# XMOS_TSBOARD_Clock.net
KiCad netlist of a schematic drawn in Altium Designer
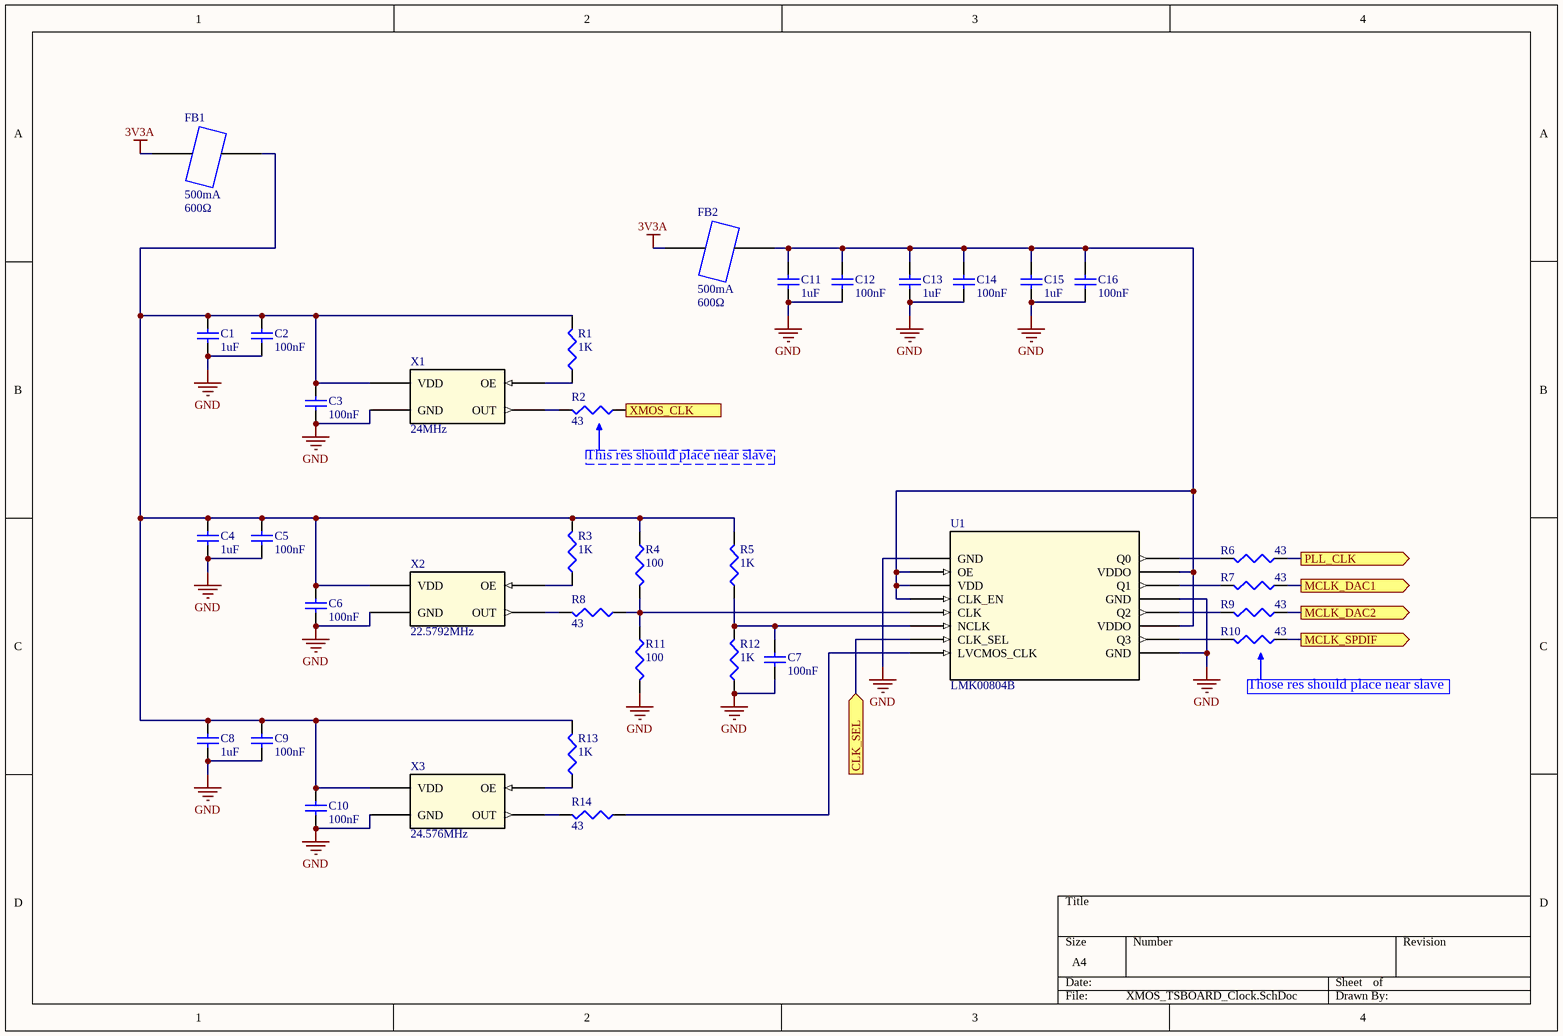
[diagram p0: XMOS_TSBOARD_Clock.SchDoc]

(export (version "E")
  (design (tool "Eeschema 10.0.6"))
  (components
    (comp (ref "C1")
      (value "1uF")
      (footprint "1608[0603]")
      (description "Capacitor (Semiconductor SIM Model)")
      (fields (field (name "Comment") "Cap Semi") (field (name "PUBLISHER") "Altium Limited"))
      (libsource (lib "Miscellaneous Devices") (part "Cap Semi"))
    )
    (comp (ref "C2")
      (value "100nF")
      (footprint "1608[0603]")
      (description "Capacitor (Semiconductor SIM Model)")
      (fields (field (name "Comment") "Cap Semi") (field (name "PUBLISHER") "Altium Limited"))
      (libsource (lib "Miscellaneous Devices") (part "Cap Semi"))
    )
    (comp (ref "C3")
      (value "100nF")
      (footprint "1608[0603]")
      (description "Capacitor (Semiconductor SIM Model)")
      (fields (field (name "Comment") "Cap Semi") (field (name "PUBLISHER") "Altium Limited"))
      (libsource (lib "Miscellaneous Devices") (part "Cap Semi"))
    )
    (comp (ref "C4")
      (value "1uF")
      (footprint "1608[0603]")
      (description "Capacitor (Semiconductor SIM Model)")
      (fields (field (name "Comment") "Cap Semi") (field (name "PUBLISHER") "Altium Limited"))
      (libsource (lib "Miscellaneous Devices") (part "Cap Semi"))
    )
    (comp (ref "C5")
      (value "100nF")
      (footprint "1608[0603]")
      (description "Capacitor (Semiconductor SIM Model)")
      (fields (field (name "Comment") "Cap Semi") (field (name "PUBLISHER") "Altium Limited"))
      (libsource (lib "Miscellaneous Devices") (part "Cap Semi"))
    )
    (comp (ref "C6")
      (value "100nF")
      (footprint "1608[0603]")
      (description "Capacitor (Semiconductor SIM Model)")
      (fields (field (name "Comment") "Cap Semi") (field (name "PUBLISHER") "Altium Limited"))
      (libsource (lib "Miscellaneous Devices") (part "Cap Semi"))
    )
    (comp (ref "C7")
      (value "100nF")
      (footprint "1608[0603]")
      (description "Capacitor (Semiconductor SIM Model)")
      (fields (field (name "Comment") "Cap Semi") (field (name "PUBLISHER") "Altium Limited"))
      (libsource (lib "Miscellaneous Devices") (part "Cap Semi"))
    )
    (comp (ref "C8")
      (value "1uF")
      (footprint "1608[0603]")
      (description "Capacitor (Semiconductor SIM Model)")
      (fields (field (name "Comment") "Cap Semi") (field (name "PUBLISHER") "Altium Limited"))
      (libsource (lib "Miscellaneous Devices") (part "Cap Semi"))
    )
    (comp (ref "C9")
      (value "100nF")
      (footprint "1608[0603]")
      (description "Capacitor (Semiconductor SIM Model)")
      (fields (field (name "Comment") "Cap Semi") (field (name "PUBLISHER") "Altium Limited"))
      (libsource (lib "Miscellaneous Devices") (part "Cap Semi"))
    )
    (comp (ref "C10")
      (value "100nF")
      (footprint "1608[0603]")
      (description "Capacitor (Semiconductor SIM Model)")
      (fields (field (name "Comment") "Cap Semi") (field (name "PUBLISHER") "Altium Limited"))
      (libsource (lib "Miscellaneous Devices") (part "Cap Semi"))
    )
    (comp (ref "C11")
      (value "1uF")
      (footprint "1608[0603]")
      (description "Capacitor (Semiconductor SIM Model)")
      (fields (field (name "Comment") "Cap Semi") (field (name "PUBLISHER") "Altium Limited"))
      (libsource (lib "Miscellaneous Devices") (part "Cap Semi"))
    )
    (comp (ref "C12")
      (value "100nF")
      (footprint "1608[0603]")
      (description "Capacitor (Semiconductor SIM Model)")
      (fields (field (name "Comment") "Cap Semi") (field (name "PUBLISHER") "Altium Limited"))
      (libsource (lib "Miscellaneous Devices") (part "Cap Semi"))
    )
    (comp (ref "C13")
      (value "1uF")
      (footprint "1608[0603]")
      (description "Capacitor (Semiconductor SIM Model)")
      (fields (field (name "Comment") "Cap Semi") (field (name "PUBLISHER") "Altium Limited"))
      (libsource (lib "Miscellaneous Devices") (part "Cap Semi"))
    )
    (comp (ref "C14")
      (value "100nF")
      (footprint "1608[0603]")
      (description "Capacitor (Semiconductor SIM Model)")
      (fields (field (name "Comment") "Cap Semi") (field (name "PUBLISHER") "Altium Limited"))
      (libsource (lib "Miscellaneous Devices") (part "Cap Semi"))
    )
    (comp (ref "C15")
      (value "1uF")
      (footprint "1608[0603]")
      (description "Capacitor (Semiconductor SIM Model)")
      (fields (field (name "Comment") "Cap Semi") (field (name "PUBLISHER") "Altium Limited"))
      (libsource (lib "Miscellaneous Devices") (part "Cap Semi"))
    )
    (comp (ref "C16")
      (value "100nF")
      (footprint "1608[0603]")
      (description "Capacitor (Semiconductor SIM Model)")
      (fields (field (name "Comment") "Cap Semi") (field (name "PUBLISHER") "Altium Limited"))
      (libsource (lib "Miscellaneous Devices") (part "Cap Semi"))
    )
    (comp (ref "FB1")
      (value "FerriteBeads")
      (footprint "0603")
      (description "Chip Ferrite Beads")
      (fields (field (name "RATEDCURRENT") "500mA") (field (name "IMPEDANCE(100MHZ)") "600Ω"))
      (libsource (lib "Troposphere_lib") (part "FerriteBeads"))
    )
    (comp (ref "FB2")
      (value "FerriteBeads")
      (footprint "0603")
      (description "Chip Ferrite Beads")
      (fields (field (name "RATEDCURRENT") "500mA") (field (name "IMPEDANCE(100MHZ)") "600Ω"))
      (libsource (lib "Troposphere_lib") (part "FerriteBeads"))
    )
    (comp (ref "R1")
      (value "1K")
      (footprint "J1-0603")
      (description "Resistor")
      (fields (field (name "Comment") "Res3") (field (name "PUBLISHER") "Altium Limited"))
      (libsource (lib "Miscellaneous Devices") (part "Res3"))
    )
    (comp (ref "R2")
      (value "43")
      (footprint "J1-0603")
      (description "Resistor")
      (fields (field (name "Comment") "Res3") (field (name "PUBLISHER") "Altium Limited"))
      (libsource (lib "Miscellaneous Devices") (part "Res3"))
    )
    (comp (ref "R3")
      (value "1K")
      (footprint "J1-0603")
      (description "Resistor")
      (fields (field (name "Comment") "Res3") (field (name "PUBLISHER") "Altium Limited"))
      (libsource (lib "Miscellaneous Devices") (part "Res3"))
    )
    (comp (ref "R4")
      (value "100")
      (footprint "J1-0603")
      (description "Resistor")
      (fields (field (name "Comment") "Res3") (field (name "PUBLISHER") "Altium Limited"))
      (libsource (lib "Miscellaneous Devices") (part "Res3"))
    )
    (comp (ref "R5")
      (value "1K")
      (footprint "J1-0603")
      (description "Resistor")
      (fields (field (name "Comment") "Res3") (field (name "PUBLISHER") "Altium Limited"))
      (libsource (lib "Miscellaneous Devices") (part "Res3"))
    )
    (comp (ref "R6")
      (value "43")
      (footprint "J1-0603")
      (description "Resistor")
      (fields (field (name "Comment") "Res3") (field (name "PUBLISHER") "Altium Limited"))
      (libsource (lib "Miscellaneous Devices") (part "Res3"))
    )
    (comp (ref "R7")
      (value "43")
      (footprint "J1-0603")
      (description "Resistor")
      (fields (field (name "Comment") "Res3") (field (name "PUBLISHER") "Altium Limited"))
      (libsource (lib "Miscellaneous Devices") (part "Res3"))
    )
    (comp (ref "R8")
      (value "43")
      (footprint "J1-0603")
      (description "Resistor")
      (fields (field (name "Comment") "Res3") (field (name "PUBLISHER") "Altium Limited"))
      (libsource (lib "Miscellaneous Devices") (part "Res3"))
    )
    (comp (ref "R9")
      (value "43")
      (footprint "J1-0603")
      (description "Resistor")
      (fields (field (name "Comment") "Res3") (field (name "PUBLISHER") "Altium Limited"))
      (libsource (lib "Miscellaneous Devices") (part "Res3"))
    )
    (comp (ref "R10")
      (value "43")
      (footprint "J1-0603")
      (description "Resistor")
      (fields (field (name "Comment") "Res3") (field (name "PUBLISHER") "Altium Limited"))
      (libsource (lib "Miscellaneous Devices") (part "Res3"))
    )
    (comp (ref "R11")
      (value "100")
      (footprint "J1-0603")
      (description "Resistor")
      (fields (field (name "Comment") "Res3") (field (name "PUBLISHER") "Altium Limited"))
      (libsource (lib "Miscellaneous Devices") (part "Res3"))
    )
    (comp (ref "R12")
      (value "1K")
      (footprint "J1-0603")
      (description "Resistor")
      (fields (field (name "Comment") "Res3") (field (name "PUBLISHER") "Altium Limited"))
      (libsource (lib "Miscellaneous Devices") (part "Res3"))
    )
    (comp (ref "R13")
      (value "1K")
      (footprint "J1-0603")
      (description "Resistor")
      (fields (field (name "Comment") "Res3") (field (name "PUBLISHER") "Altium Limited"))
      (libsource (lib "Miscellaneous Devices") (part "Res3"))
    )
    (comp (ref "R14")
      (value "43")
      (footprint "J1-0603")
      (description "Resistor")
      (fields (field (name "Comment") "Res3") (field (name "PUBLISHER") "Altium Limited"))
      (libsource (lib "Miscellaneous Devices") (part "Res3"))
    )
    (comp (ref "U1")
      (value "LMK00804B")
      (footprint "PW16")
      (description "Low Skew, 1-to-4 Multiplexed Differential/LVCMOS-to-LVCMOS/TTL Fanout Buffer")
      (libsource (lib "Troposphere_lib") (part "LMK00804B"))
    )
    (comp (ref "X1")
      (value "SiT8208")
      (footprint "7050")
      (description "Ultra Performance Oscillator")
      (fields (field (name "FREQUENCY") "24MHz"))
      (libsource (lib "Troposphere_lib") (part "SiT8208"))
    )
    (comp (ref "X2")
      (value "SiT8208")
      (footprint "7050")
      (description "Ultra Performance Oscillator")
      (fields (field (name "FREQUENCY") "22.5792MHz"))
      (libsource (lib "Troposphere_lib") (part "SiT8208"))
    )
    (comp (ref "X3")
      (value "SiT8208")
      (footprint "7050")
      (description "Ultra Performance Oscillator")
      (fields (field (name "FREQUENCY") "24.576MHz"))
      (libsource (lib "Troposphere_lib") (part "SiT8208"))
    )
  )
  (nets
    (net (code "1") (name "/CLK_SEL") (class "Default")
      (node (ref "U1") (pin "7") (pinfunction "CLK_SEL_7") (pintype "input"))
    )
    (net (code "2") (name "/MCLK_DAC1") (class "Default")
      (node (ref "R7") (pin "1") (pinfunction "1_1") (pintype "passive"))
    )
    (net (code "3") (name "/MCLK_DAC2") (class "Default")
      (node (ref "R9") (pin "1") (pinfunction "1_1") (pintype "passive"))
    )
    (net (code "4") (name "/MCLK_SPDIF") (class "Default")
      (node (ref "R10") (pin "1") (pinfunction "1_1") (pintype "passive"))
    )
    (net (code "5") (name "/PLL_CLK") (class "Default")
      (node (ref "R6") (pin "1") (pinfunction "1_1") (pintype "passive"))
    )
    (net (code "6") (name "/XMOS_CLK") (class "Default")
      (node (ref "R2") (pin "1") (pinfunction "1_1") (pintype "passive"))
    )
    (net (code "7") (name "3V3A") (class "Default")
      (node (ref "FB1") (pin "1") (pinfunction "1_1") (pintype "power_in"))
      (node (ref "FB2") (pin "1") (pinfunction "1_1") (pintype "power_in"))
    )
    (net (code "8") (name "GND") (class "Default")
      (node (ref "C1") (pin "1") (pinfunction "1_1") (pintype "passive"))
      (node (ref "C10") (pin "1") (pinfunction "1_1") (pintype "passive"))
      (node (ref "C11") (pin "1") (pinfunction "1_1") (pintype "passive"))
      (node (ref "C12") (pin "1") (pinfunction "1_1") (pintype "passive"))
      (node (ref "C13") (pin "1") (pinfunction "1_1") (pintype "passive"))
      (node (ref "C14") (pin "1") (pinfunction "1_1") (pintype "passive"))
      (node (ref "C15") (pin "1") (pinfunction "1_1") (pintype "passive"))
      (node (ref "C16") (pin "1") (pinfunction "1_1") (pintype "passive"))
      (node (ref "C2") (pin "1") (pinfunction "1_1") (pintype "passive"))
      (node (ref "C3") (pin "1") (pinfunction "1_1") (pintype "passive"))
      (node (ref "C4") (pin "1") (pinfunction "1_1") (pintype "passive"))
      (node (ref "C5") (pin "1") (pinfunction "1_1") (pintype "passive"))
      (node (ref "C6") (pin "1") (pinfunction "1_1") (pintype "passive"))
      (node (ref "C7") (pin "1") (pinfunction "1_1") (pintype "passive"))
      (node (ref "C8") (pin "1") (pinfunction "1_1") (pintype "passive"))
      (node (ref "C9") (pin "1") (pinfunction "1_1") (pintype "passive"))
      (node (ref "R11") (pin "2") (pinfunction "2_2") (pintype "passive"))
      (node (ref "R12") (pin "1") (pinfunction "1_1") (pintype "passive"))
      (node (ref "U1") (pin "1") (pinfunction "GND_1") (pintype "power_in"))
      (node (ref "U1") (pin "13") (pinfunction "GND_13") (pintype "power_in"))
      (node (ref "U1") (pin "9") (pinfunction "GND_9") (pintype "power_in"))
      (node (ref "X1") (pin "2") (pinfunction "GND_2") (pintype "power_in"))
      (node (ref "X2") (pin "2") (pinfunction "GND_2") (pintype "power_in"))
      (node (ref "X3") (pin "2") (pinfunction "GND_2") (pintype "power_in"))
    )
    (net (code "9") (name "Net-(U1-CLK)") (class "Default")
      (node (ref "R11") (pin "1") (pinfunction "1_1") (pintype "passive"))
      (node (ref "R4") (pin "2") (pinfunction "2_2") (pintype "passive"))
      (node (ref "R8") (pin "1") (pinfunction "1_1") (pintype "passive"))
      (node (ref "U1") (pin "5") (pinfunction "CLK_5") (pintype "input"))
    )
    (net (code "10") (name "Net-(U1-CLK_EN)") (class "Default")
      (node (ref "C11") (pin "2") (pinfunction "2_2") (pintype "passive"))
      (node (ref "C12") (pin "2") (pinfunction "2_2") (pintype "passive"))
      (node (ref "C13") (pin "2") (pinfunction "2_2") (pintype "passive"))
      (node (ref "C14") (pin "2") (pinfunction "2_2") (pintype "passive"))
      (node (ref "C15") (pin "2") (pinfunction "2_2") (pintype "passive"))
      (node (ref "C16") (pin "2") (pinfunction "2_2") (pintype "passive"))
      (node (ref "FB2") (pin "2") (pinfunction "2_2") (pintype "power_in"))
      (node (ref "U1") (pin "11") (pinfunction "VDDO_11") (pintype "power_in"))
      (node (ref "U1") (pin "15") (pinfunction "VDDO_15") (pintype "power_in"))
      (node (ref "U1") (pin "2") (pinfunction "OE_2") (pintype "input"))
      (node (ref "U1") (pin "3") (pinfunction "VDD_3") (pintype "power_in"))
      (node (ref "U1") (pin "4") (pinfunction "CLK_EN_4") (pintype "input"))
    )
    (net (code "11") (name "Net-(U1-LVCMOS_CLK)") (class "Default")
      (node (ref "R14") (pin "1") (pinfunction "1_1") (pintype "passive"))
      (node (ref "U1") (pin "8") (pinfunction "LVCMOS_CLK_8") (pintype "input"))
    )
    (net (code "12") (name "Net-(U1-NCLK)") (class "Default")
      (node (ref "C7") (pin "2") (pinfunction "2_2") (pintype "passive"))
      (node (ref "R12") (pin "2") (pinfunction "2_2") (pintype "passive"))
      (node (ref "R5") (pin "1") (pinfunction "1_1") (pintype "passive"))
      (node (ref "U1") (pin "6") (pinfunction "NCLK_6") (pintype "input"))
    )
    (net (code "13") (name "Net-(U1-Q0)") (class "Default")
      (node (ref "R6") (pin "2") (pinfunction "2_2") (pintype "passive"))
      (node (ref "U1") (pin "16") (pinfunction "Q0_16") (pintype "output"))
    )
    (net (code "14") (name "Net-(U1-Q1)") (class "Default")
      (node (ref "R7") (pin "2") (pinfunction "2_2") (pintype "passive"))
      (node (ref "U1") (pin "14") (pinfunction "Q1_14") (pintype "output"))
    )
    (net (code "15") (name "Net-(U1-Q2)") (class "Default")
      (node (ref "R9") (pin "2") (pinfunction "2_2") (pintype "passive"))
      (node (ref "U1") (pin "12") (pinfunction "Q2_12") (pintype "output"))
    )
    (net (code "16") (name "Net-(U1-Q3)") (class "Default")
      (node (ref "R10") (pin "2") (pinfunction "2_2") (pintype "passive"))
      (node (ref "U1") (pin "10") (pinfunction "Q3_10") (pintype "output"))
    )
    (net (code "17") (name "Net-(X1-OE)") (class "Default")
      (node (ref "R1") (pin "1") (pinfunction "1_1") (pintype "passive"))
      (node (ref "X1") (pin "1") (pinfunction "OE_1") (pintype "input"))
    )
    (net (code "18") (name "Net-(X1-OUT)") (class "Default")
      (node (ref "R2") (pin "2") (pinfunction "2_2") (pintype "passive"))
      (node (ref "X1") (pin "3") (pinfunction "OUT_3") (pintype "output"))
    )
    (net (code "19") (name "Net-(X1-VDD)") (class "Default")
      (node (ref "C1") (pin "2") (pinfunction "2_2") (pintype "passive"))
      (node (ref "C10") (pin "2") (pinfunction "2_2") (pintype "passive"))
      (node (ref "C2") (pin "2") (pinfunction "2_2") (pintype "passive"))
      (node (ref "C3") (pin "2") (pinfunction "2_2") (pintype "passive"))
      (node (ref "C4") (pin "2") (pinfunction "2_2") (pintype "passive"))
      (node (ref "C5") (pin "2") (pinfunction "2_2") (pintype "passive"))
      (node (ref "C6") (pin "2") (pinfunction "2_2") (pintype "passive"))
      (node (ref "C8") (pin "2") (pinfunction "2_2") (pintype "passive"))
      (node (ref "C9") (pin "2") (pinfunction "2_2") (pintype "passive"))
      (node (ref "FB1") (pin "2") (pinfunction "2_2") (pintype "power_in"))
      (node (ref "R1") (pin "2") (pinfunction "2_2") (pintype "passive"))
      (node (ref "R13") (pin "2") (pinfunction "2_2") (pintype "passive"))
      (node (ref "R3") (pin "2") (pinfunction "2_2") (pintype "passive"))
      (node (ref "R4") (pin "1") (pinfunction "1_1") (pintype "passive"))
      (node (ref "R5") (pin "2") (pinfunction "2_2") (pintype "passive"))
      (node (ref "X1") (pin "4") (pinfunction "VDD_4") (pintype "power_in"))
      (node (ref "X2") (pin "4") (pinfunction "VDD_4") (pintype "power_in"))
      (node (ref "X3") (pin "4") (pinfunction "VDD_4") (pintype "power_in"))
    )
    (net (code "20") (name "Net-(X2-OE)") (class "Default")
      (node (ref "R3") (pin "1") (pinfunction "1_1") (pintype "passive"))
      (node (ref "X2") (pin "1") (pinfunction "OE_1") (pintype "input"))
    )
    (net (code "21") (name "Net-(X2-OUT)") (class "Default")
      (node (ref "R8") (pin "2") (pinfunction "2_2") (pintype "passive"))
      (node (ref "X2") (pin "3") (pinfunction "OUT_3") (pintype "output"))
    )
    (net (code "22") (name "Net-(X3-OE)") (class "Default")
      (node (ref "R13") (pin "1") (pinfunction "1_1") (pintype "passive"))
      (node (ref "X3") (pin "1") (pinfunction "OE_1") (pintype "input"))
    )
    (net (code "23") (name "Net-(X3-OUT)") (class "Default")
      (node (ref "R14") (pin "2") (pinfunction "2_2") (pintype "passive"))
      (node (ref "X3") (pin "3") (pinfunction "OUT_3") (pintype "output"))
    )
  )
)
